# Principal.net
KiCad netlist of a schematic drawn in Altium Designer
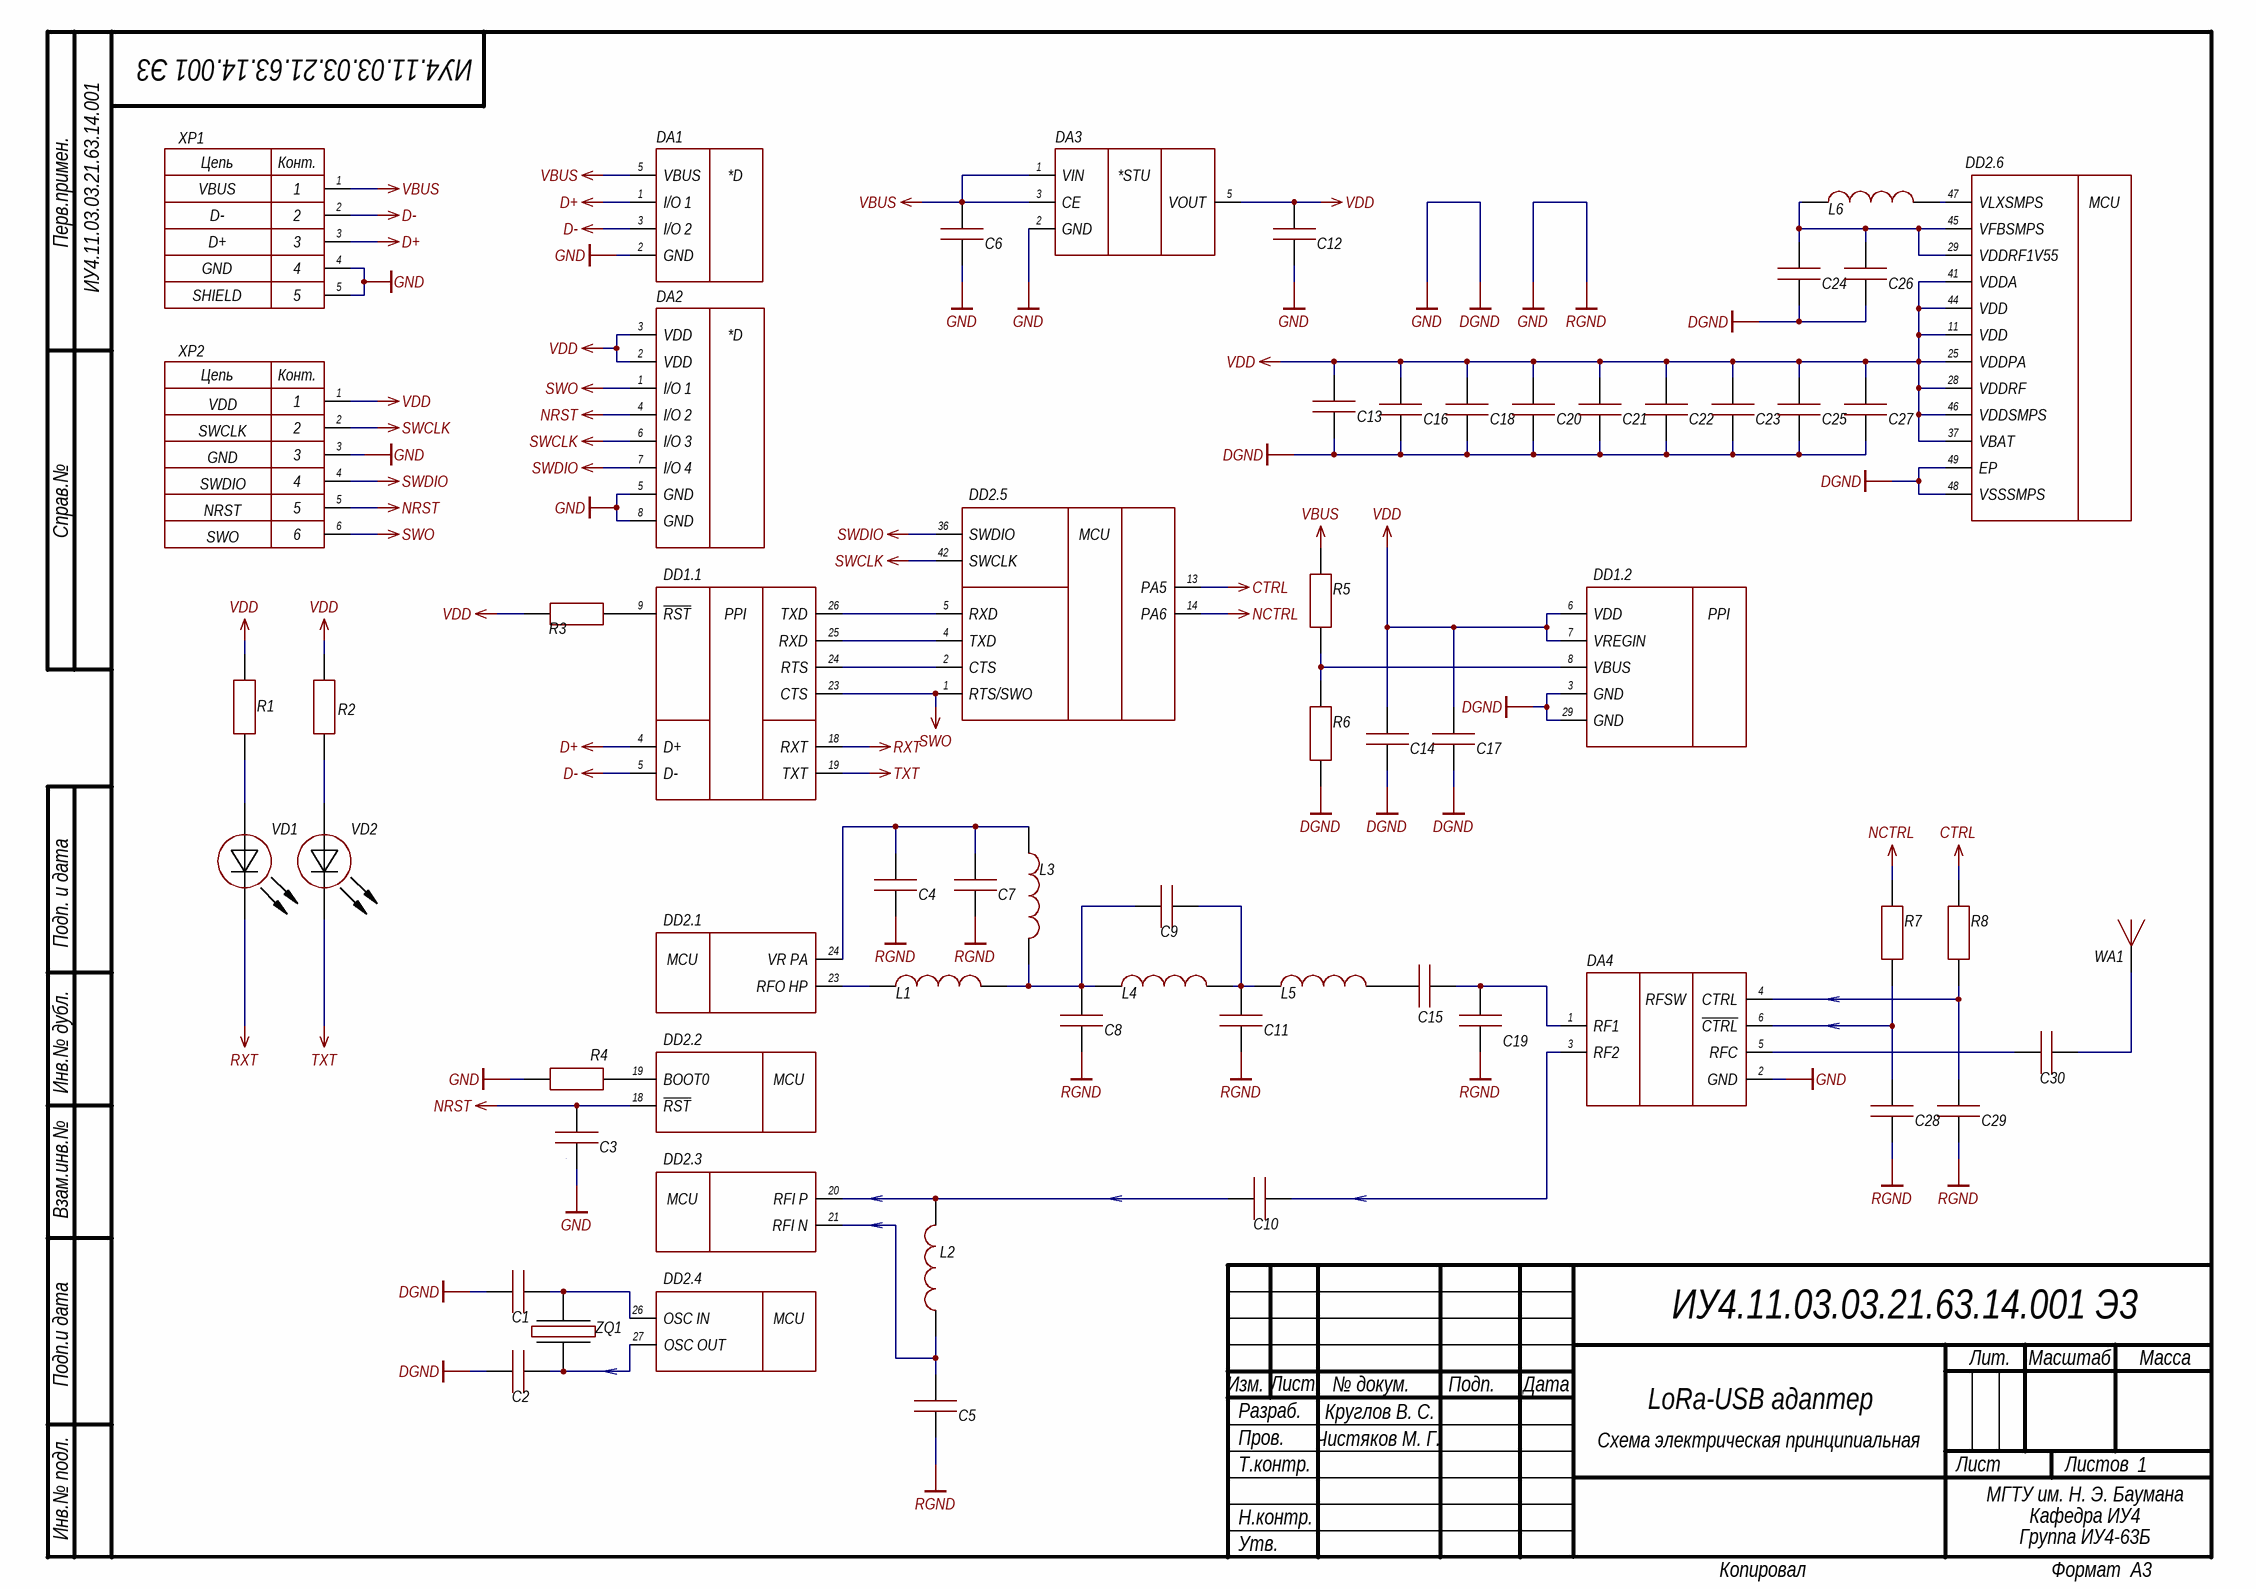
[diagram p0: Principal.SchDoc]

(export (version "E")
  (design (tool "Eeschema 10.0.6"))
  (components
    (comp (ref "C1")
      (value "04023J0R9BBWTR")
      (footprint "CAP: 0402")
      (fields (field (name "MANUFACTURER") "AVX Interconnect / Elco"))
      (libsource (lib "Components - 25.02.24 - 15.21") (part "C"))
    )
    (comp (ref "C2")
      (value "04023J0R9BBWTR")
      (footprint "CAP: 0402")
      (fields (field (name "MANUFACTURER") "AVX Interconnect / Elco"))
      (libsource (lib "Components - 25.02.24 - 15.21") (part "C"))
    )
    (comp (ref "C3")
      (value "04023J0R9BBWTR")
      (footprint "CAP: 0402")
      (fields (field (name "MANUFACTURER") "AVX Interconnect / Elco"))
      (libsource (lib "Components - 25.02.24 - 15.21") (part "C"))
    )
    (comp (ref "C4")
      (value "04023J0R9BBWTR")
      (footprint "CAP: 0402")
      (fields (field (name "MANUFACTURER") "AVX Interconnect / Elco"))
      (libsource (lib "Components - 25.02.24 - 15.21") (part "C"))
    )
    (comp (ref "C5")
      (value "04023J0R9BBWTR")
      (footprint "CAP: 0402")
      (fields (field (name "MANUFACTURER") "AVX Interconnect / Elco"))
      (libsource (lib "Components - 25.02.24 - 15.21") (part "C"))
    )
    (comp (ref "C6")
      (value "04023J0R9BBWTR")
      (footprint "CAP: 0402")
      (fields (field (name "MANUFACTURER") "AVX Interconnect / Elco"))
      (libsource (lib "Components - 25.02.24 - 15.21") (part "C"))
    )
    (comp (ref "C7")
      (value "04023J0R9BBWTR")
      (footprint "CAP: 0402")
      (fields (field (name "MANUFACTURER") "AVX Interconnect / Elco"))
      (libsource (lib "Components - 25.02.24 - 15.21") (part "C"))
    )
    (comp (ref "C8")
      (value "04023J0R9BBWTR")
      (footprint "CAP: 0402")
      (fields (field (name "MANUFACTURER") "AVX Interconnect / Elco"))
      (libsource (lib "Components - 25.02.24 - 15.21") (part "C"))
    )
    (comp (ref "C9")
      (value "04023J0R9BBWTR")
      (footprint "CAP: 0402")
      (fields (field (name "MANUFACTURER") "AVX Interconnect / Elco"))
      (libsource (lib "Components - 25.02.24 - 15.21") (part "C"))
    )
    (comp (ref "C10")
      (value "04023J0R9BBWTR")
      (footprint "CAP: 0402")
      (fields (field (name "MANUFACTURER") "AVX Interconnect / Elco"))
      (libsource (lib "Components - 25.02.24 - 15.21") (part "C"))
    )
    (comp (ref "C11")
      (value "04023J0R9BBWTR")
      (footprint "CAP: 0402")
      (fields (field (name "MANUFACTURER") "AVX Interconnect / Elco"))
      (libsource (lib "Components - 25.02.24 - 15.21") (part "C"))
    )
    (comp (ref "C12")
      (value "04023J0R9BBWTR")
      (footprint "CAP: 0402")
      (fields (field (name "MANUFACTURER") "AVX Interconnect / Elco"))
      (libsource (lib "Components - 25.02.24 - 15.21") (part "C"))
    )
    (comp (ref "C13")
      (value "04023J0R9BBWTR")
      (footprint "CAP: 0402")
      (fields (field (name "MANUFACTURER") "AVX Interconnect / Elco"))
      (libsource (lib "Components - 25.02.24 - 15.21") (part "C"))
    )
    (comp (ref "C14")
      (value "04023J0R9BBWTR")
      (footprint "CAP: 0402")
      (fields (field (name "MANUFACTURER") "AVX Interconnect / Elco"))
      (libsource (lib "Components - 25.02.24 - 15.21") (part "C"))
    )
    (comp (ref "C15")
      (value "04023J0R9BBWTR")
      (footprint "CAP: 0402")
      (fields (field (name "MANUFACTURER") "AVX Interconnect / Elco"))
      (libsource (lib "Components - 25.02.24 - 15.21") (part "C"))
    )
    (comp (ref "C16")
      (value "04023J0R9BBWTR")
      (footprint "CAP: 0402")
      (fields (field (name "MANUFACTURER") "AVX Interconnect / Elco"))
      (libsource (lib "Components - 25.02.24 - 15.21") (part "C"))
    )
    (comp (ref "C17")
      (value "04023J0R9BBWTR")
      (footprint "CAP: 0402")
      (fields (field (name "MANUFACTURER") "AVX Interconnect / Elco"))
      (libsource (lib "Components - 25.02.24 - 15.21") (part "C"))
    )
    (comp (ref "C18")
      (value "04023J0R9BBWTR")
      (footprint "CAP: 0402")
      (fields (field (name "MANUFACTURER") "AVX Interconnect / Elco"))
      (libsource (lib "Components - 25.02.24 - 15.21") (part "C"))
    )
    (comp (ref "C19")
      (value "04023J0R9BBWTR")
      (footprint "CAP: 0402")
      (fields (field (name "MANUFACTURER") "AVX Interconnect / Elco"))
      (libsource (lib "Components - 25.02.24 - 15.21") (part "C"))
    )
    (comp (ref "C20")
      (value "04023J0R9BBWTR")
      (footprint "CAP: 0402")
      (fields (field (name "MANUFACTURER") "AVX Interconnect / Elco"))
      (libsource (lib "Components - 25.02.24 - 15.21") (part "C"))
    )
    (comp (ref "C21")
      (value "04023J0R9BBWTR")
      (footprint "CAP: 0402")
      (fields (field (name "MANUFACTURER") "AVX Interconnect / Elco"))
      (libsource (lib "Components - 25.02.24 - 15.21") (part "C"))
    )
    (comp (ref "C22")
      (value "04023J0R9BBWTR")
      (footprint "CAP: 0402")
      (fields (field (name "MANUFACTURER") "AVX Interconnect / Elco"))
      (libsource (lib "Components - 25.02.24 - 15.21") (part "C"))
    )
    (comp (ref "C23")
      (value "04023J0R9BBWTR")
      (footprint "CAP: 0402")
      (fields (field (name "MANUFACTURER") "AVX Interconnect / Elco"))
      (libsource (lib "Components - 25.02.24 - 15.21") (part "C"))
    )
    (comp (ref "C24")
      (value "04023J0R9BBWTR")
      (footprint "CAP: 0402")
      (fields (field (name "MANUFACTURER") "AVX Interconnect / Elco"))
      (libsource (lib "Components - 25.02.24 - 15.21") (part "C"))
    )
    (comp (ref "C25")
      (value "04023J0R9BBWTR")
      (footprint "CAP: 0402")
      (fields (field (name "MANUFACTURER") "AVX Interconnect / Elco"))
      (libsource (lib "Components - 25.02.24 - 15.21") (part "C"))
    )
    (comp (ref "C26")
      (value "04023J0R9BBWTR")
      (footprint "CAP: 0402")
      (fields (field (name "MANUFACTURER") "AVX Interconnect / Elco"))
      (libsource (lib "Components - 25.02.24 - 15.21") (part "C"))
    )
    (comp (ref "C27")
      (value "04023J0R9BBWTR")
      (footprint "CAP: 0402")
      (fields (field (name "MANUFACTURER") "AVX Interconnect / Elco"))
      (libsource (lib "Components - 25.02.24 - 15.21") (part "C"))
    )
    (comp (ref "C28")
      (value "04023J0R9BBWTR")
      (footprint "CAP: 0402")
      (fields (field (name "MANUFACTURER") "AVX Interconnect / Elco"))
      (libsource (lib "Components - 25.02.24 - 15.21") (part "C"))
    )
    (comp (ref "C29")
      (value "04023J0R9BBWTR")
      (footprint "CAP: 0402")
      (fields (field (name "MANUFACTURER") "AVX Interconnect / Elco"))
      (libsource (lib "Components - 25.02.24 - 15.21") (part "C"))
    )
    (comp (ref "C30")
      (value "04023J0R9BBWTR")
      (footprint "CAP: 0402")
      (fields (field (name "MANUFACTURER") "AVX Interconnect / Elco"))
      (libsource (lib "Components - 25.02.24 - 15.21") (part "C"))
    )
    (comp (ref "DA1")
      (value "SRV05-4.TCT")
      (footprint "SMTC-SOT23-6_V")
      (fields (field (name "MANUFACTURER") "Semtech"))
      (libsource (lib "Course") (part "CMP-2000-05358-1"))
    )
    (comp (ref "DA2")
      (value "SRDA3.3-4DR2G")
      (footprint "8-SOIC")
      (fields (field (name "MANUFACTURER") "On Semiconductor"))
      (libsource (lib "Components - 17.03.24 - 18.35") (part "CMP-1063-00128-1"))
    )
    (comp (ref "DA3")
      (value "XC6219B332MR")
      (footprint "SOT23-5")
      (description "LDO Voltage Regulators 0.3A, 3.3V")
      (libsource (lib "Course") (part "STU"))
    )
    (comp (ref "DA4")
      (value "HMC544AETR")
      (footprint "FP-RJ-6-IPC_C")
      (description "IC RF SWITCH SPDT 4GHZ SOT26")
      (libsource (lib "Components - 26.03.24 - 17.25") (part "CMP-09141-000069-1"))
    )
    (comp (ref "DD1")
      (value "CP2102N-A02-GQFN28R")
      (footprint "FP-CP2102N-A02-GQFN28R-IPC_C")
      (description "IC USB TO UART BRIDGE QFN28")
      (libsource (lib "Course") (part "CMP-08093-000007-1"))
    )
    (comp (ref "DD2")
      (value "STM32WLE5CCU6")
      (footprint "FP-UFQFPN48-A0B9-MFG")
      (description "MULTIPROTOCOL LPWAN 32-BIT ARM C")
      (libsource (lib "Components - 25.02.24 - 14.16") (part "CMP-12105-000100-1"))
    )
    (comp (ref "L1")
      (value "LQW15AN4N3C00D")
      (footprint "IND: 0402")
      (description "Wire Wound RF Inductor 4.3nH ±0.2nH 750mA 0.07Ω 0402 (1005)")
      (libsource (lib "Components - 25.02.24 - 15.24") (part "L"))
    )
    (comp (ref "L2")
      (value "LQW15AN4N3C00D")
      (footprint "IND: 0402")
      (description "Wire Wound RF Inductor 4.3nH ±0.2nH 750mA 0.07Ω 0402 (1005)")
      (libsource (lib "Components - 25.02.24 - 15.24") (part "L"))
    )
    (comp (ref "L3")
      (value "LQW15AN4N3C00D")
      (footprint "IND: 0402")
      (description "Wire Wound RF Inductor 4.3nH ±0.2nH 750mA 0.07Ω 0402 (1005)")
      (libsource (lib "Components - 25.02.24 - 15.24") (part "L"))
    )
    (comp (ref "L4")
      (value "LQW15AN4N3C00D")
      (footprint "IND: 0402")
      (description "Wire Wound RF Inductor 4.3nH ±0.2nH 750mA 0.07Ω 0402 (1005)")
      (libsource (lib "Components - 25.02.24 - 15.24") (part "L"))
    )
    (comp (ref "L5")
      (value "LQW15AN4N3C00D")
      (footprint "IND: 0402")
      (description "Wire Wound RF Inductor 4.3nH ±0.2nH 750mA 0.07Ω 0402 (1005)")
      (libsource (lib "Components - 25.02.24 - 15.24") (part "L"))
    )
    (comp (ref "L6")
      (value "LQW15AN4N3C00D")
      (footprint "IND: 0402")
      (description "Wire Wound RF Inductor 4.3nH ±0.2nH 750mA 0.07Ω 0402 (1005)")
      (libsource (lib "Components - 25.02.24 - 15.24") (part "L"))
    )
    (comp (ref "R1")
      (value "RC0402FR-074K7L")
      (footprint "RES: 0402")
      (fields (field (name "MANUFACTURER") "Yageo / Phycomp"))
      (libsource (lib "Components - 25.02.24 - 15.13") (part "R"))
    )
    (comp (ref "R2")
      (value "RC0402FR-074K7L")
      (footprint "RES: 0402")
      (fields (field (name "MANUFACTURER") "Yageo / Phycomp"))
      (libsource (lib "Components - 25.02.24 - 15.13") (part "R"))
    )
    (comp (ref "R3")
      (value "RC0402FR-074K7L")
      (footprint "RES: 0402")
      (fields (field (name "MANUFACTURER") "Yageo / Phycomp"))
      (libsource (lib "Components - 25.02.24 - 15.13") (part "R"))
    )
    (comp (ref "R4")
      (value "RC0402FR-074K7L")
      (footprint "RES: 0402")
      (fields (field (name "MANUFACTURER") "Yageo / Phycomp"))
      (libsource (lib "Components - 25.02.24 - 15.13") (part "R"))
    )
    (comp (ref "R5")
      (value "RC0402FR-074K7L")
      (footprint "RES: 0402")
      (fields (field (name "MANUFACTURER") "Yageo / Phycomp"))
      (libsource (lib "Components - 25.02.24 - 15.13") (part "R"))
    )
    (comp (ref "R6")
      (value "RC0402FR-074K7L")
      (footprint "RES: 0402")
      (fields (field (name "MANUFACTURER") "Yageo / Phycomp"))
      (libsource (lib "Components - 25.02.24 - 15.13") (part "R"))
    )
    (comp (ref "R7")
      (value "RC0402FR-074K7L")
      (footprint "RES: 0402")
      (fields (field (name "MANUFACTURER") "Yageo / Phycomp"))
      (libsource (lib "Components - 25.02.24 - 15.13") (part "R"))
    )
    (comp (ref "R8")
      (value "RC0402FR-074K7L")
      (footprint "RES: 0402")
      (fields (field (name "MANUFACTURER") "Yageo / Phycomp"))
      (libsource (lib "Components - 25.02.24 - 15.13") (part "R"))
    )
    (comp (ref "VD1")
      (value "~")
      (footprint "LED: 0805R")
      (fields (field (name "VALUEMANUFACTURERPARTNUMBER") "LED, Green, *, *, *, -55...+150°C"))
      (libsource (lib "Course") (part "LED_single"))
    )
    (comp (ref "VD2")
      (value "~")
      (footprint "LED: 0805G")
      (fields (field (name "VALUEMANUFACTURERPARTNUMBER") "LED, Green, *, *, *, -55...+150°C"))
      (libsource (lib "Course") (part "LED_single"))
    )
    (comp (ref "WA1") (value "Antenna") (footprint "ANTENNA") (libsource (lib "Course") (part "Antenna")))
    (comp (ref "XP1")
      (value "480-37-1000")
      (footprint "MOLX-480-37-1000_V")
      (fields (field (name "TOLERANCE") "1%"))
      (libsource (lib "Course") (part "USB-A plug"))
    )
    (comp (ref "XP2")
      (value "Connector PLS-6")
      (footprint "PLS-6")
      (libsource (lib "Course") (part "Connector PLS-6"))
    )
    (comp (ref "ZQ1") (value "*") (footprint "OSC: 2016") (libsource (lib "Course") (part "Oscillator")))
  )
  (nets
    (net (code "1") (name "CTRL") (class "Default")
      (node (ref "DD2") (pin "13") (pinfunction "PA5_13") (pintype "power_in"))
      (node (ref "R8") (pin "1") (pinfunction "1_1") (pintype "passive"))
    )
    (net (code "2") (name "D+") (class "Default")
      (node (ref "DA1") (pin "1") (pinfunction "I/O_1_1") (pintype "passive"))
      (node (ref "DD1") (pin "4") (pinfunction "D+_4") (pintype "power_in"))
      (node (ref "XP1") (pin "3") (pinfunction "D+_3") (pintype "passive"))
    )
    (net (code "3") (name "D-") (class "Default")
      (node (ref "DA1") (pin "3") (pinfunction "I/O_2_3") (pintype "passive"))
      (node (ref "DD1") (pin "5") (pinfunction "D-_5") (pintype "power_in"))
      (node (ref "XP1") (pin "2") (pinfunction "D-_2") (pintype "passive"))
    )
    (net (code "4") (name "DGND") (class "Default")
      (node (ref "C1") (pin "1") (pinfunction "1_1") (pintype "passive"))
      (node (ref "C11") (pin "1") (pinfunction "1_1") (pintype "passive"))
      (node (ref "C12") (pin "2") (pinfunction "2_2") (pintype "passive"))
      (node (ref "C13") (pin "2") (pinfunction "2_2") (pintype "passive"))
      (node (ref "C14") (pin "2") (pinfunction "2_2") (pintype "passive"))
      (node (ref "C16") (pin "2") (pinfunction "2_2") (pintype "passive"))
      (node (ref "C17") (pin "2") (pinfunction "2_2") (pintype "passive"))
      (node (ref "C18") (pin "2") (pinfunction "2_2") (pintype "passive"))
      (node (ref "C19") (pin "1") (pinfunction "1_1") (pintype "passive"))
      (node (ref "C2") (pin "1") (pinfunction "1_1") (pintype "passive"))
      (node (ref "C20") (pin "2") (pinfunction "2_2") (pintype "passive"))
      (node (ref "C21") (pin "2") (pinfunction "2_2") (pintype "passive"))
      (node (ref "C22") (pin "2") (pinfunction "2_2") (pintype "passive"))
      (node (ref "C23") (pin "2") (pinfunction "2_2") (pintype "passive"))
      (node (ref "C24") (pin "2") (pinfunction "2_2") (pintype "passive"))
      (node (ref "C25") (pin "2") (pinfunction "2_2") (pintype "passive"))
      (node (ref "C26") (pin "2") (pinfunction "2_2") (pintype "passive"))
      (node (ref "C27") (pin "2") (pinfunction "2_2") (pintype "passive"))
      (node (ref "C28") (pin "1") (pinfunction "1_1") (pintype "passive"))
      (node (ref "C29") (pin "1") (pinfunction "1_1") (pintype "passive"))
      (node (ref "C3") (pin "1") (pinfunction "1_1") (pintype "passive"))
      (node (ref "C4") (pin "1") (pinfunction "1_1") (pintype "passive"))
      (node (ref "C5") (pin "1") (pinfunction "1_1") (pintype "passive"))
      (node (ref "C6") (pin "2") (pinfunction "2_2") (pintype "passive"))
      (node (ref "C7") (pin "1") (pinfunction "1_1") (pintype "passive"))
      (node (ref "C8") (pin "1") (pinfunction "1_1") (pintype "passive"))
      (node (ref "DA1") (pin "2") (pinfunction "GND_2") (pintype "passive"))
      (node (ref "DA2") (pin "5") (pinfunction "GND_5") (pintype "power_in"))
      (node (ref "DA2") (pin "8") (pinfunction "GND_8") (pintype "power_in"))
      (node (ref "DA3") (pin "2") (pinfunction "GND_2") (pintype "power_in"))
      (node (ref "DA4") (pin "2") (pinfunction "GND_2") (pintype "passive"))
      (node (ref "DD1") (pin "29") (pinfunction "GND_29") (pintype "power_in"))
      (node (ref "DD1") (pin "3") (pinfunction "GND_3") (pintype "power_in"))
      (node (ref "DD2") (pin "48") (pinfunction "VSSSMPS_48") (pintype "power_in"))
      (node (ref "DD2") (pin "49") (pinfunction "EP_49") (pintype "power_in"))
      (node (ref "R4") (pin "2") (pinfunction "2_2") (pintype "passive"))
      (node (ref "R6") (pin "1") (pinfunction "1_1") (pintype "passive"))
      (node (ref "XP1") (pin "4") (pinfunction "GND_4") (pintype "passive"))
      (node (ref "XP1") (pin "5") (pinfunction "SHLD_5") (pintype "passive"))
      (node (ref "XP2") (pin "3") (pintype "passive"))
    )
    (net (code "5") (name "NCTRL") (class "Default")
      (node (ref "DD2") (pin "14") (pinfunction "PA6_14") (pintype "power_in"))
      (node (ref "R7") (pin "1") (pinfunction "1_1") (pintype "passive"))
    )
    (net (code "6") (name "NRST") (class "Default")
      (node (ref "C3") (pin "2") (pinfunction "2_2") (pintype "passive"))
      (node (ref "DA2") (pin "4") (pinfunction "I/O_2_4") (pintype "passive"))
      (node (ref "DD2") (pin "18") (pinfunction "~{RST}_18") (pintype "power_in"))
      (node (ref "XP2") (pin "5") (pintype "passive"))
    )
    (net (code "7") (name "Net-(C8-Pad2)") (class "Default")
      (node (ref "C8") (pin "2") (pinfunction "2_2") (pintype "passive"))
      (node (ref "C9") (pin "2") (pinfunction "2_2") (pintype "passive"))
      (node (ref "L1") (pin "2") (pinfunction "2_2") (pintype "passive"))
      (node (ref "L3") (pin "2") (pinfunction "2_2") (pintype "passive"))
      (node (ref "L4") (pin "1") (pinfunction "1_1") (pintype "passive"))
    )
    (net (code "8") (name "Net-(C11-Pad2)") (class "Default")
      (node (ref "C11") (pin "2") (pinfunction "2_2") (pintype "passive"))
      (node (ref "C9") (pin "1") (pinfunction "1_1") (pintype "passive"))
      (node (ref "L4") (pin "2") (pinfunction "2_2") (pintype "passive"))
      (node (ref "L5") (pin "1") (pinfunction "1_1") (pintype "passive"))
    )
    (net (code "9") (name "Net-(C15-Pad1)") (class "Default")
      (node (ref "C15") (pin "1") (pinfunction "1_1") (pintype "passive"))
      (node (ref "L5") (pin "2") (pinfunction "2_2") (pintype "passive"))
    )
    (net (code "10") (name "Net-(C30-Pad1)") (class "Default")
      (node (ref "C30") (pin "1") (pinfunction "1_1") (pintype "passive"))
      (node (ref "WA1") (pin "1") (pinfunction "1_1") (pintype "passive"))
    )
    (net (code "11") (name "Net-(DA4-CTRL)") (class "Default")
      (node (ref "C29") (pin "2") (pinfunction "2_2") (pintype "passive"))
      (node (ref "DA4") (pin "4") (pinfunction "CTRL_4") (pintype "passive"))
      (node (ref "R8") (pin "2") (pinfunction "2_2") (pintype "passive"))
    )
    (net (code "12") (name "Net-(DA4-RF1)") (class "Default")
      (node (ref "C15") (pin "2") (pinfunction "2_2") (pintype "passive"))
      (node (ref "C19") (pin "2") (pinfunction "2_2") (pintype "passive"))
      (node (ref "DA4") (pin "1") (pinfunction "RF1_1") (pintype "passive"))
    )
    (net (code "13") (name "Net-(DA4-RF2)") (class "Default")
      (node (ref "C10") (pin "1") (pinfunction "1_1") (pintype "passive"))
      (node (ref "DA4") (pin "3") (pinfunction "RF2_3") (pintype "passive"))
    )
    (net (code "14") (name "Net-(DA4-RFC)") (class "Default")
      (node (ref "C30") (pin "2") (pinfunction "2_2") (pintype "passive"))
      (node (ref "DA4") (pin "5") (pinfunction "RFC_5") (pintype "passive"))
    )
    (net (code "15") (name "Net-(DA4-~{CTRL})") (class "Default")
      (node (ref "C28") (pin "2") (pinfunction "2_2") (pintype "passive"))
      (node (ref "DA4") (pin "6") (pinfunction "~{CTRL}_6") (pintype "passive"))
      (node (ref "R7") (pin "2") (pinfunction "2_2") (pintype "passive"))
    )
    (net (code "16") (name "Net-(DD1A-VBUS)") (class "Default")
      (node (ref "DD1") (pin "8") (pinfunction "VBUS_8") (pintype "power_in"))
      (node (ref "R5") (pin "1") (pinfunction "1_1") (pintype "passive"))
      (node (ref "R6") (pin "2") (pinfunction "2_2") (pintype "passive"))
    )
    (net (code "17") (name "Net-(DD1B-RTS)") (class "Default")
      (node (ref "DD1") (pin "24") (pinfunction "RTS_24") (pintype "power_in"))
      (node (ref "DD2") (pin "2") (pinfunction "CTS_2") (pintype "power_in"))
    )
    (net (code "18") (name "Net-(DD1B-RXD)") (class "Default")
      (node (ref "DD1") (pin "25") (pinfunction "RXD_25") (pintype "power_in"))
      (node (ref "DD2") (pin "4") (pinfunction "TXD_4") (pintype "power_in"))
    )
    (net (code "19") (name "Net-(DD1B-TXD)") (class "Default")
      (node (ref "DD1") (pin "26") (pinfunction "TXD_26") (pintype "power_in"))
      (node (ref "DD2") (pin "5") (pinfunction "RXD_5") (pintype "power_in"))
    )
    (net (code "20") (name "Net-(DD1B-~{RST})") (class "Default")
      (node (ref "DD1") (pin "9") (pinfunction "~{RST}_9") (pintype "power_in"))
      (node (ref "R3") (pin "2") (pinfunction "2_2") (pintype "passive"))
    )
    (net (code "21") (name "Net-(DD2A-VDDRF1V55)") (class "Default")
      (node (ref "C24") (pin "1") (pinfunction "1_1") (pintype "passive"))
      (node (ref "C26") (pin "1") (pinfunction "1_1") (pintype "passive"))
      (node (ref "DD2") (pin "29") (pinfunction "VDDRF1V55_29") (pintype "power_in"))
      (node (ref "DD2") (pin "45") (pinfunction "VFBSMPS_45") (pintype "power_in"))
      (node (ref "L6") (pin "1") (pinfunction "1_1") (pintype "passive"))
    )
    (net (code "22") (name "Net-(DD2A-VLXSMPS)") (class "Default")
      (node (ref "DD2") (pin "47") (pinfunction "VLXSMPS_47") (pintype "power_in"))
      (node (ref "L6") (pin "2") (pinfunction "2_2") (pintype "passive"))
    )
    (net (code "23") (name "Net-(DD2C-OSC_IN)") (class "Default")
      (node (ref "C1") (pin "2") (pinfunction "2_2") (pintype "passive"))
      (node (ref "DD2") (pin "26") (pinfunction "OSC_IN_26") (pintype "passive"))
      (node (ref "ZQ1") (pin "3") (pinfunction "3_3") (pintype "passive"))
    )
    (net (code "24") (name "Net-(DD2C-OSC_OUT)") (class "Default")
      (node (ref "C2") (pin "2") (pinfunction "2_2") (pintype "passive"))
      (node (ref "DD2") (pin "27") (pinfunction "OSC_OUT_27") (pintype "passive"))
      (node (ref "ZQ1") (pin "1") (pinfunction "1_1") (pintype "passive"))
    )
    (net (code "25") (name "Net-(DD2D-BOOT0)") (class "Default")
      (node (ref "DD2") (pin "19") (pinfunction "BOOT0_19") (pintype "power_in"))
      (node (ref "R4") (pin "1") (pinfunction "1_1") (pintype "passive"))
    )
    (net (code "26") (name "Net-(DD2E-RFO_HP)") (class "Default")
      (node (ref "DD2") (pin "23") (pinfunction "RFO_HP_23") (pintype "passive"))
      (node (ref "L1") (pin "1") (pinfunction "1_1") (pintype "passive"))
    )
    (net (code "27") (name "Net-(DD2E-VR_PA)") (class "Default")
      (node (ref "C4") (pin "2") (pinfunction "2_2") (pintype "passive"))
      (node (ref "C7") (pin "2") (pinfunction "2_2") (pintype "passive"))
      (node (ref "DD2") (pin "24") (pinfunction "VR_PA_24") (pintype "power_in"))
      (node (ref "L3") (pin "1") (pinfunction "1_1") (pintype "passive"))
    )
    (net (code "28") (name "Net-(DD2F-RFI_N)") (class "Default")
      (node (ref "C5") (pin "2") (pinfunction "2_2") (pintype "passive"))
      (node (ref "DD2") (pin "21") (pinfunction "RFI_N_21") (pintype "passive"))
      (node (ref "L2") (pin "1") (pinfunction "1_1") (pintype "passive"))
    )
    (net (code "29") (name "Net-(DD2F-RFI_P)") (class "Default")
      (node (ref "C10") (pin "2") (pinfunction "2_2") (pintype "passive"))
      (node (ref "DD2") (pin "20") (pinfunction "RFI_P_20") (pintype "passive"))
      (node (ref "L2") (pin "2") (pinfunction "2_2") (pintype "passive"))
    )
    (net (code "30") (name "Net-(VD1-A)") (class "Default")
      (node (ref "R1") (pin "2") (pinfunction "2_2") (pintype "passive"))
      (node (ref "VD1") (pin "1") (pinfunction "A_1") (pintype "passive"))
    )
    (net (code "31") (name "Net-(VD2-A)") (class "Default")
      (node (ref "R2") (pin "2") (pinfunction "2_2") (pintype "passive"))
      (node (ref "VD2") (pin "1") (pinfunction "A_1") (pintype "passive"))
    )
    (net (code "32") (name "RXT") (class "Default")
      (node (ref "DD1") (pin "18") (pinfunction "RXT_18") (pintype "power_in"))
      (node (ref "VD1") (pin "2") (pinfunction "C_2") (pintype "passive"))
    )
    (net (code "33") (name "SWCLK") (class "Default")
      (node (ref "DA2") (pin "6") (pinfunction "I/O_3_6") (pintype "passive"))
      (node (ref "DD2") (pin "42") (pinfunction "SWCLK_42") (pintype "power_in"))
      (node (ref "XP2") (pin "2") (pintype "passive"))
    )
    (net (code "34") (name "SWDIO") (class "Default")
      (node (ref "DA2") (pin "7") (pinfunction "I/O_4_7") (pintype "passive"))
      (node (ref "DD2") (pin "36") (pinfunction "SWDIO_36") (pintype "power_in"))
      (node (ref "XP2") (pin "4") (pintype "passive"))
    )
    (net (code "35") (name "SWO") (class "Default")
      (node (ref "DA2") (pin "1") (pinfunction "I/O_1_1") (pintype "passive"))
      (node (ref "DD1") (pin "23") (pinfunction "CTS_23") (pintype "power_in"))
      (node (ref "DD2") (pin "1") (pinfunction "RTS/SWO_1") (pintype "power_in"))
      (node (ref "XP2") (pin "6") (pintype "passive"))
    )
    (net (code "36") (name "TXT") (class "Default")
      (node (ref "DD1") (pin "19") (pinfunction "TXT_19") (pintype "power_in"))
      (node (ref "VD2") (pin "2") (pinfunction "C_2") (pintype "passive"))
    )
    (net (code "37") (name "VBUS") (class "Default")
      (node (ref "C6") (pin "1") (pinfunction "1_1") (pintype "passive"))
      (node (ref "DA1") (pin "5") (pinfunction "VBUS_5") (pintype "passive"))
      (node (ref "DA3") (pin "1") (pinfunction "VIN_1") (pintype "power_in"))
      (node (ref "DA3") (pin "3") (pinfunction "CE_3") (pintype "passive"))
      (node (ref "R5") (pin "2") (pinfunction "2_2") (pintype "passive"))
      (node (ref "XP1") (pin "1") (pinfunction "VBUS_1") (pintype "passive"))
    )
    (net (code "38") (name "VDD") (class "Default")
      (node (ref "C12") (pin "1") (pinfunction "1_1") (pintype "passive"))
      (node (ref "C13") (pin "1") (pinfunction "1_1") (pintype "passive"))
      (node (ref "C14") (pin "1") (pinfunction "1_1") (pintype "passive"))
      (node (ref "C16") (pin "1") (pinfunction "1_1") (pintype "passive"))
      (node (ref "C17") (pin "1") (pinfunction "1_1") (pintype "passive"))
      (node (ref "C18") (pin "1") (pinfunction "1_1") (pintype "passive"))
      (node (ref "C20") (pin "1") (pinfunction "1_1") (pintype "passive"))
      (node (ref "C21") (pin "1") (pinfunction "1_1") (pintype "passive"))
      (node (ref "C22") (pin "1") (pinfunction "1_1") (pintype "passive"))
      (node (ref "C23") (pin "1") (pinfunction "1_1") (pintype "passive"))
      (node (ref "C25") (pin "1") (pinfunction "1_1") (pintype "passive"))
      (node (ref "C27") (pin "1") (pinfunction "1_1") (pintype "passive"))
      (node (ref "DA2") (pin "2") (pinfunction "VDD_2") (pintype "passive"))
      (node (ref "DA2") (pin "3") (pinfunction "VDD_3") (pintype "passive"))
      (node (ref "DA3") (pin "5") (pinfunction "VOUT_5") (pintype "passive"))
      (node (ref "DD1") (pin "6") (pinfunction "VDD_6") (pintype "power_in"))
      (node (ref "DD1") (pin "7") (pinfunction "VREGIN_7") (pintype "power_in"))
      (node (ref "DD2") (pin "11") (pinfunction "VDD_11") (pintype "power_in"))
      (node (ref "DD2") (pin "25") (pinfunction "VDDPA_25") (pintype "power_in"))
      (node (ref "DD2") (pin "28") (pinfunction "VDDRF_28") (pintype "power_in"))
      (node (ref "DD2") (pin "37") (pinfunction "VBAT_37") (pintype "power_in"))
      (node (ref "DD2") (pin "41") (pinfunction "VDDA_41") (pintype "power_in"))
      (node (ref "DD2") (pin "44") (pinfunction "VDD_44") (pintype "power_in"))
      (node (ref "DD2") (pin "46") (pinfunction "VDDSMPS_46") (pintype "power_in"))
      (node (ref "R1") (pin "1") (pinfunction "1_1") (pintype "passive"))
      (node (ref "R2") (pin "1") (pinfunction "1_1") (pintype "passive"))
      (node (ref "R3") (pin "1") (pinfunction "1_1") (pintype "passive"))
      (node (ref "XP2") (pin "1") (pintype "passive"))
    )
  )
)
